# Gyro.net
KiCad netlist of a schematic drawn in Altium Designer
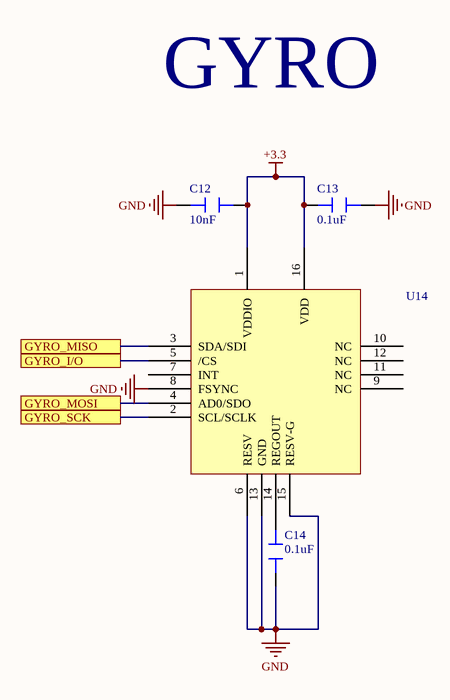
[diagram p0: Gyro.SchDoc]

(export (version "E")
  (design (tool "Eeschema 10.0.6"))
  (components
    (comp (ref "C12")
      (value "10nF")
      (footprint "CAPACITOR 0805")
      (description "Multilayer Ceramic Capacitors MLCC - SMD/SMT .01uF 50volts 10%")
      (fields
        (field (name "MANUFACTURER") "Vishay Vitramon")
        (field (name "MANUFACTURER PART NUMBER") "VJ0805Y103KXAAC")
      )
      (libsource (lib "BiricuticoBonito") (part "Capacitor  10nF 0805"))
    )
    (comp (ref "C13")
      (value "0.1uF")
      (footprint "CAPACITOR 0805")
      (description "Multilayer Ceramic Capacitors MLCC - SMD/SMT .1uF 50volts 10%")
      (fields
        (field (name "MANUFACTURER") "Vishay Vitramon")
        (field (name "MANUFACTURER PART NUMBER") "VJ0805Y104KXAAT")
      )
      (libsource (lib "BiricuticoBonito") (part "Capacitor  0.1uF 0805"))
    )
    (comp (ref "C14")
      (value "0.1uF")
      (footprint "CAPACITOR 0805")
      (description "Multilayer Ceramic Capacitors MLCC - SMD/SMT .1uF 50volts 10%")
      (fields
        (field (name "MANUFACTURER") "Vishay Vitramon")
        (field (name "MANUFACTURER PART NUMBER") "VJ0805Y104KXAAT")
      )
      (libsource (lib "BiricuticoBonito") (part "Capacitor  0.1uF 0805"))
    )
    (comp (ref "U14")
      (value "Gyroscope")
      (footprint "GYROSCOPE")
      (description "MEMS GYROSCOPE 1-AXIS 16QFN")
      (fields
        (field (name "MANUFACTURER") "TDK InvenSense")
        (field (name "MANUFACTURER PART NUMBER") "ISZ-2510")
      )
      (libsource (lib "BiricuticoBonito") (part "Gyroscope"))
    )
  )
  (nets
    (net (code "1") (name "+3.3") (class "Default")
      (node (ref "C12") (pin "2") (pinfunction "34_2") (pintype "passive"))
      (node (ref "C13") (pin "1") (pinfunction "33_1") (pintype "passive"))
      (node (ref "U14") (pin "1") (pinfunction "VDDIO_1") (pintype "passive"))
      (node (ref "U14") (pin "16") (pinfunction "VDD_16") (pintype "passive"))
    )
    (net (code "2") (name "/GYRO_I{slash}O") (class "Default")
      (node (ref "U14") (pin "5") (pinfunction "/CS_5") (pintype "passive"))
    )
    (net (code "3") (name "/GYRO_MISO") (class "Default")
      (node (ref "U14") (pin "3") (pinfunction "SDA/SDI_3") (pintype "passive"))
    )
    (net (code "4") (name "/GYRO_MOSI") (class "Default")
      (node (ref "U14") (pin "4") (pinfunction "AD0/SDO_4") (pintype "passive"))
    )
    (net (code "5") (name "/GYRO_SCK") (class "Default")
      (node (ref "U14") (pin "2") (pinfunction "SCL/SCLK_2") (pintype "passive"))
    )
    (net (code "6") (name "GND") (class "Default")
      (node (ref "C12") (pin "1") (pinfunction "33_1") (pintype "passive"))
      (node (ref "C13") (pin "2") (pinfunction "34_2") (pintype "passive"))
      (node (ref "C14") (pin "1") (pinfunction "33_1") (pintype "passive"))
      (node (ref "U14") (pin "13") (pinfunction "GND_13") (pintype "passive"))
      (node (ref "U14") (pin "15") (pinfunction "RESV-G_15") (pintype "passive"))
      (node (ref "U14") (pin "6") (pinfunction "RESV_6") (pintype "passive"))
      (node (ref "U14") (pin "8") (pinfunction "FSYNC_8") (pintype "passive"))
    )
    (net (code "7") (name "Net-(C14-34)") (class "Default")
      (node (ref "C14") (pin "2") (pinfunction "34_2") (pintype "passive"))
      (node (ref "U14") (pin "14") (pinfunction "REGOUT_14") (pintype "passive"))
    )
    (net (code "8") (name "unconnected-(U14-INT-Pad7)") (class "Default")
      (node (ref "U14") (pin "7") (pinfunction "INT_7") (pintype "passive"))
    )
    (net (code "9") (name "unconnected-(U14-NC-Pad9)") (class "Default")
      (node (ref "U14") (pin "9") (pinfunction "NC_9") (pintype "passive"))
    )
    (net (code "10") (name "unconnected-(U14-NC-Pad10)") (class "Default")
      (node (ref "U14") (pin "10") (pinfunction "NC_10") (pintype "passive"))
    )
    (net (code "11") (name "unconnected-(U14-NC-Pad11)") (class "Default")
      (node (ref "U14") (pin "11") (pinfunction "NC_11") (pintype "passive"))
    )
    (net (code "12") (name "unconnected-(U14-NC-Pad12)") (class "Default")
      (node (ref "U14") (pin "12") (pinfunction "NC_12") (pintype "passive"))
    )
  )
)
